# PCB-SW-2PB-35-1_1-in-wall-IoT-Switch-Boa.net
KiCad netlist of a schematic drawn in EAGLE
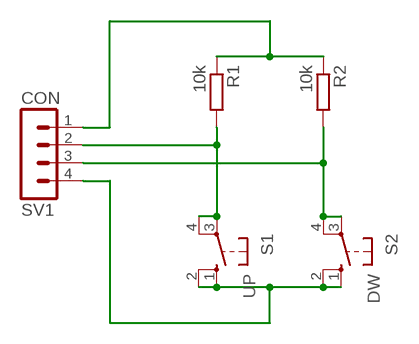
[diagram p0: schematic, sheet 1]

(export (version "E")
  (design (tool "Eeschema 10.0.6"))
  (components
    (comp (ref "R1")
      (value "10k")
      (footprint "eagle-import:R1206W")
      (libsource (lib "eagle-import") (part "R-EU_R1206W"))
    )
    (comp (ref "R2")
      (value "10k")
      (footprint "eagle-import:R1206W")
      (libsource (lib "eagle-import") (part "R-EU_R1206W"))
    )
    (comp (ref "S1")
      (value "UP")
      (footprint "eagle-import:B3F-40XX")
      (fields (field (name "MF") "OMRON COMPONENTS USA") (field (name "MPN") "B3F-4000"))
      (libsource (lib "eagle-import") (part "40-XX"))
    )
    (comp (ref "S2")
      (value "DW")
      (footprint "eagle-import:B3F-40XX")
      (fields (field (name "MF") "OMRON COMPONENTS USA") (field (name "MPN") "B3F-4000"))
      (libsource (lib "eagle-import") (part "40-XX"))
    )
    (comp (ref "SV1")
      (value "CON")
      (footprint "eagle-import:MA04-1")
      (libsource (lib "eagle-import") (part "MA04-1"))
    )
  )
  (nets
    (net (code "1") (name "Net-(R1-Pad1)") (class "Default")
      (node (ref "R1") (pin "1") (pinfunction "1_1") (pintype "passive"))
      (node (ref "R2") (pin "1") (pinfunction "1_1") (pintype "passive"))
      (node (ref "SV1") (pin "1") (pinfunction "1_1") (pintype "passive"))
    )
    (net (code "2") (name "Net-(S1-P)") (class "Default")
      (node (ref "R1") (pin "2") (pinfunction "2_2") (pintype "passive"))
      (node (ref "S1") (pin "3") (pinfunction "P_3") (pintype "passive"))
      (node (ref "S1") (pin "4") (pinfunction "P1_4") (pintype "passive"))
      (node (ref "SV1") (pin "2") (pinfunction "2_2") (pintype "passive"))
    )
    (net (code "3") (name "Net-(S1-S)") (class "Default")
      (node (ref "S1") (pin "1") (pinfunction "S_1") (pintype "passive"))
      (node (ref "S1") (pin "2") (pinfunction "S1_2") (pintype "passive"))
      (node (ref "S2") (pin "1") (pinfunction "S_1") (pintype "passive"))
      (node (ref "S2") (pin "2") (pinfunction "S1_2") (pintype "passive"))
      (node (ref "SV1") (pin "4") (pinfunction "4_4") (pintype "passive"))
    )
    (net (code "4") (name "Net-(S2-P)") (class "Default")
      (node (ref "R2") (pin "2") (pinfunction "2_2") (pintype "passive"))
      (node (ref "S2") (pin "3") (pinfunction "P_3") (pintype "passive"))
      (node (ref "S2") (pin "4") (pinfunction "P1_4") (pintype "passive"))
      (node (ref "SV1") (pin "3") (pinfunction "3_3") (pintype "passive"))
    )
  )
)
